# GPIO_Expander_Sheet.net
KiCad netlist of a schematic drawn in Altium Designer
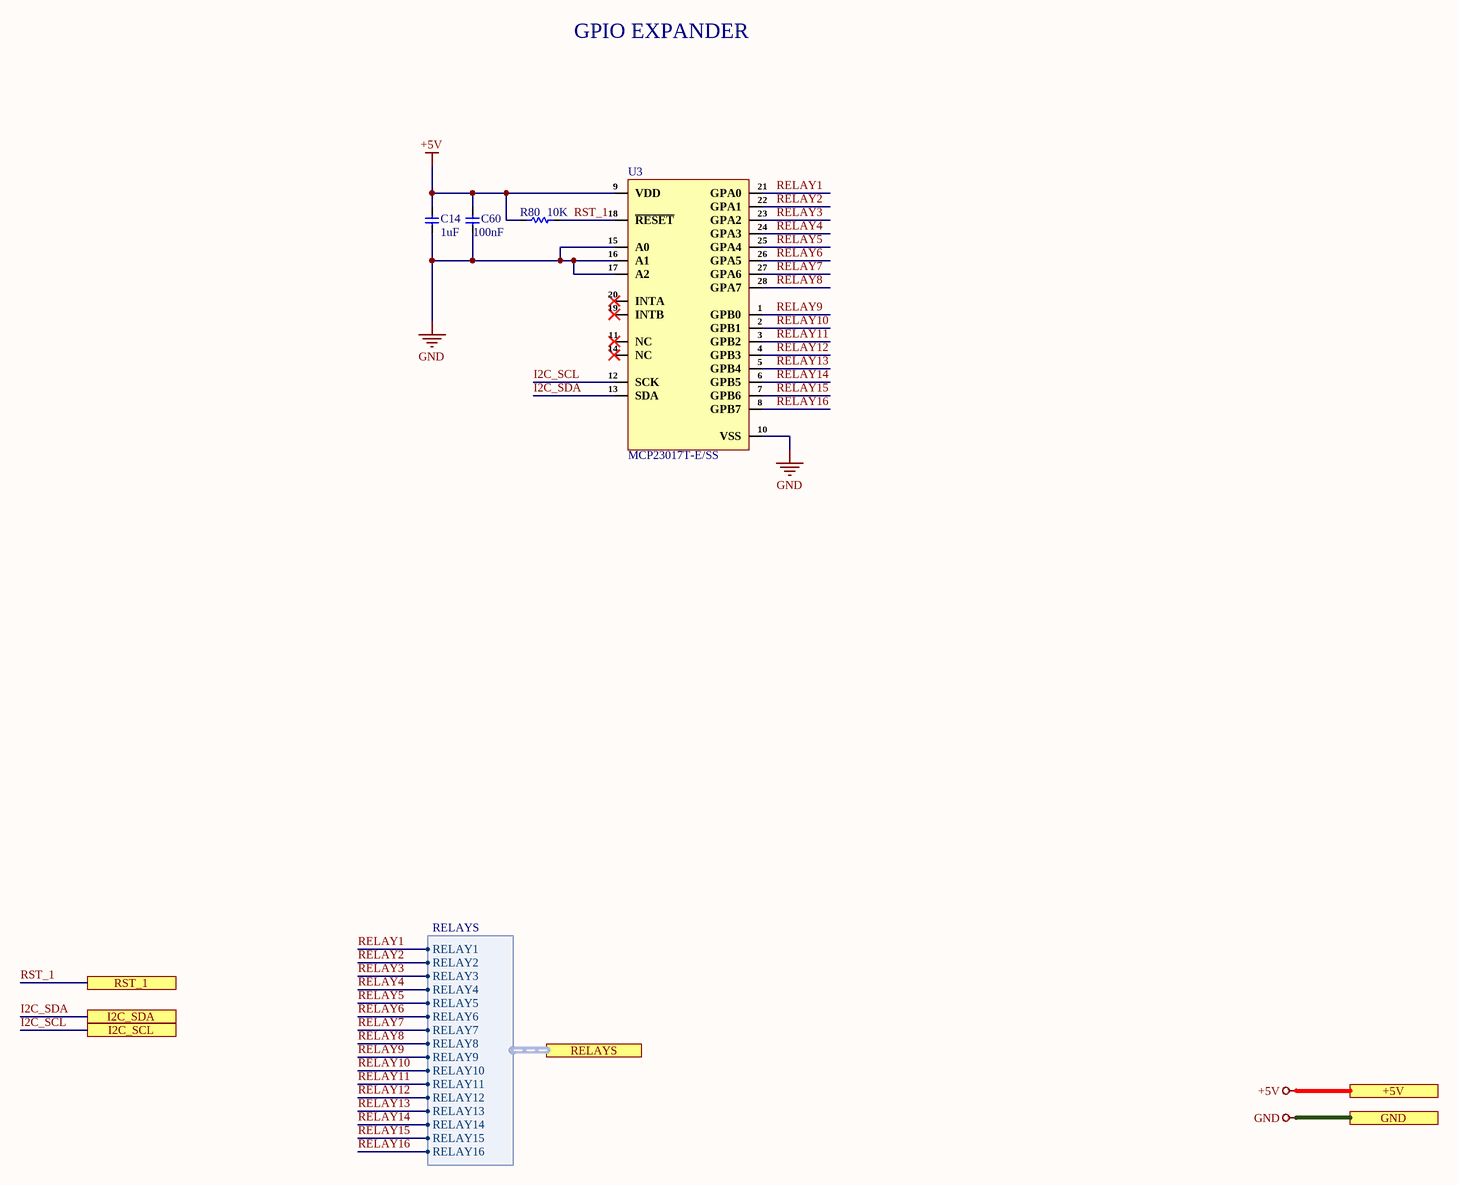
[diagram p0: GPIO_Expander_Sheet.SchDoc]

(export (version "E")
  (design (tool "Eeschema 10.0.6"))
  (components
    (comp (ref "C14")
      (value "1uF")
      (footprint "Cap-0402")
      (description "CAP CER 1UF 10V X5R 0402")
      (fields
        (field (name "MANUFACTURER") "Yageo")
        (field (name "MANUFACTURER PART NUMBER") "CC0402KRX5R6BB105")
      )
      (libsource (lib "eSpark Libraries") (part "CC0402KRX5R6BB105"))
    )
    (comp (ref "C60")
      (value "100nF")
      (footprint "cap-0402")
      (description "CAP CER 0.1UF 50V X7R 0402")
      (fields
        (field (name "MANUFACTURER") "TDK")
        (field (name "MANUFACTURER PART NUMBER") "C1005X7R1H104KT000F")
      )
      (libsource (lib "eSpark Libraries") (part "C1005X7R1H104KT000F"))
    )
    (comp (ref "R80")
      (value "10K")
      (footprint "Res-0402")
      (description "RES 10K OHM 1% 1/16W 0402")
      (fields
        (field (name "MANUFACTURER") "Yageo")
        (field (name "MANUFACTURER PART NUMBER") "RC0402FR-0710KL")
      )
      (libsource (lib "eSpark Libraries") (part "RC0402FR-0710KL"))
    )
    (comp (ref "U3")
      (value "MCP23017T-E/SS")
      (footprint "SSOP-28-208mil")
      (description "IC XPNDR 1.7MHZ I2C 28SSOP")
      (fields (field (name "MANUFACTURER") "Microchip") (field (name "LCSC PART NUMBER") "C558584"))
      (libsource (lib "eSpark Libraries") (part "MCP23017T-E/SS"))
    )
  )
  (nets
    (net (code "2") (name "+5V") (class "Default")
      (node (ref "C14") (pin "2") (pinfunction "2_2") (pintype "passive"))
      (node (ref "C60") (pin "2") (pinfunction "2_2") (pintype "passive"))
      (node (ref "R80") (pin "2") (pinfunction "2_2") (pintype "passive"))
      (node (ref "U3") (pin "9") (pinfunction "VDD_9") (pintype "passive"))
    )
    (net (code "3") (name "/I2C_SCL") (class "Default")
      (node (ref "U3") (pin "12") (pinfunction "SCK_12") (pintype "passive"))
    )
    (net (code "4") (name "/I2C_SDA") (class "Default")
      (node (ref "U3") (pin "13") (pinfunction "SDA_13") (pintype "passive"))
    )
    (net (code "5") (name "/RELAY1") (class "Default")
      (node (ref "U3") (pin "21") (pinfunction "GPA0_21") (pintype "passive"))
    )
    (net (code "6") (name "/RELAY2") (class "Default")
      (node (ref "U3") (pin "22") (pinfunction "GPA1_22") (pintype "passive"))
    )
    (net (code "7") (name "/RELAY3") (class "Default")
      (node (ref "U3") (pin "23") (pinfunction "GPA2_23") (pintype "passive"))
    )
    (net (code "8") (name "/RELAY4") (class "Default")
      (node (ref "U3") (pin "24") (pinfunction "GPA3_24") (pintype "passive"))
    )
    (net (code "9") (name "/RELAY5") (class "Default")
      (node (ref "U3") (pin "25") (pinfunction "GPA4_25") (pintype "passive"))
    )
    (net (code "10") (name "/RELAY6") (class "Default")
      (node (ref "U3") (pin "26") (pinfunction "GPA5_26") (pintype "passive"))
    )
    (net (code "11") (name "/RELAY7") (class "Default")
      (node (ref "U3") (pin "27") (pinfunction "GPA6_27") (pintype "passive"))
    )
    (net (code "12") (name "/RELAY8") (class "Default")
      (node (ref "U3") (pin "28") (pinfunction "GPA7_28") (pintype "passive"))
    )
    (net (code "13") (name "/RELAY9") (class "Default")
      (node (ref "U3") (pin "1") (pinfunction "GPB0_1") (pintype "passive"))
    )
    (net (code "14") (name "/RELAY10") (class "Default")
      (node (ref "U3") (pin "2") (pinfunction "GPB1_2") (pintype "passive"))
    )
    (net (code "15") (name "/RELAY11") (class "Default")
      (node (ref "U3") (pin "3") (pinfunction "GPB2_3") (pintype "passive"))
    )
    (net (code "16") (name "/RELAY12") (class "Default")
      (node (ref "U3") (pin "4") (pinfunction "GPB3_4") (pintype "passive"))
    )
    (net (code "17") (name "/RELAY13") (class "Default")
      (node (ref "U3") (pin "5") (pinfunction "GPB4_5") (pintype "passive"))
    )
    (net (code "18") (name "/RELAY14") (class "Default")
      (node (ref "U3") (pin "6") (pinfunction "GPB5_6") (pintype "passive"))
    )
    (net (code "19") (name "/RELAY15") (class "Default")
      (node (ref "U3") (pin "7") (pinfunction "GPB6_7") (pintype "passive"))
    )
    (net (code "20") (name "/RELAY16") (class "Default")
      (node (ref "U3") (pin "8") (pinfunction "GPB7_8") (pintype "passive"))
    )
    (net (code "21") (name "/RST_1") (class "Default")
      (node (ref "R80") (pin "1") (pinfunction "1_1") (pintype "passive"))
      (node (ref "U3") (pin "18") (pinfunction "~{RESET}_18") (pintype "passive"))
    )
    (net (code "23") (name "GND") (class "Default")
      (node (ref "C14") (pin "1") (pinfunction "1_1") (pintype "passive"))
      (node (ref "C60") (pin "1") (pinfunction "1_1") (pintype "passive"))
      (node (ref "U3") (pin "10") (pinfunction "VSS_10") (pintype "passive"))
      (node (ref "U3") (pin "15") (pinfunction "A0_15") (pintype "passive"))
      (node (ref "U3") (pin "16") (pinfunction "A1_16") (pintype "passive"))
      (node (ref "U3") (pin "17") (pinfunction "A2_17") (pintype "passive"))
    )
    (net (code "24") (name "unconnected-(U3-INTA-Pad20)") (class "Default")
      (node (ref "U3") (pin "20") (pinfunction "INTA_20") (pintype "passive+no_connect"))
    )
    (net (code "25") (name "unconnected-(U3-INTB-Pad19)") (class "Default")
      (node (ref "U3") (pin "19") (pinfunction "INTB_19") (pintype "passive+no_connect"))
    )
    (net (code "26") (name "unconnected-(U3-NC-Pad11)") (class "Default")
      (node (ref "U3") (pin "11") (pinfunction "NC_11") (pintype "passive+no_connect"))
    )
    (net (code "27") (name "unconnected-(U3-NC-Pad14)") (class "Default")
      (node (ref "U3") (pin "14") (pinfunction "NC_14") (pintype "passive+no_connect"))
    )
  )
)
